# OR_GATE.net
KiCad netlist of a schematic drawn in Altium Designer
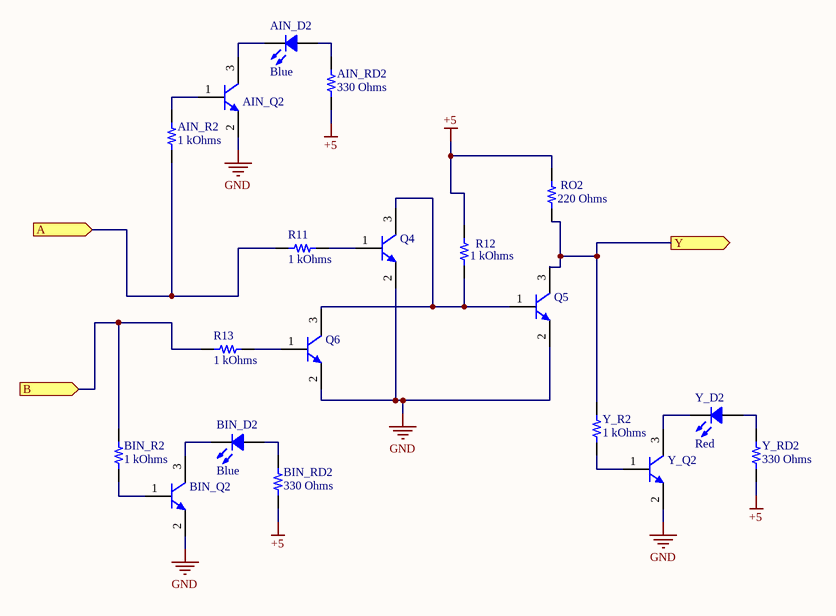
[diagram p0: OR_GATE.SchDoc]

(export (version "E")
  (design (tool "Eeschema 10.0.6"))
  (components
    (comp (ref "AIN_D2")
      (value "Blue")
      (footprint "LED 0603_1608 BLUE")
      (description "LED BLUE CLEAR 0603 SMD")
      (fields (field (name "PART NUMBER") "IN-S63AT5B") (field (name "MANUFACTURER") "Inolux"))
      (libsource (lib "Celestial Altium Library - altium_library") (part "LED"))
    )
    (comp (ref "AIN_Q2")
      (value "MMSS8050-L-TP")
      (footprint "MCCSEMI SOT-23-3")
      (description "TRANS NPN 25V 1.5A SOT23")
      (fields (field (name "MANUFACTURER") "Micro Commercial Co"))
      (libsource (lib "Celestial Altium Library - altium_library") (part "MCCSEMI NPN SOT-23-3"))
    )
    (comp (ref "AIN_R2")
      (value "1 kOhms")
      (footprint "RES 0603_1608")
      (description "RES SMD 1K OHM 0.1% 1/16W 0603")
      (fields
        (field (name "PART NUMBER") "CPF0603B1K0E")
        (field (name "MANUFACTURER") "TE Connectivity Passive Product")
      )
      (libsource (lib "Celestial Altium Library - altium_library") (part "Resistor"))
    )
    (comp (ref "AIN_RD2")
      (value "330 Ohms")
      (footprint "RES 0603_1608")
      (description "RES 330 OHM 5% 1/10W 0603")
      (fields
        (field (name "PART NUMBER") "RMCF0603JT330R")
        (field (name "MANUFACTURER") "Stackpole Electronics Inc")
      )
      (libsource (lib "Celestial Altium Library - altium_library") (part "Resistor"))
    )
    (comp (ref "BIN_D2")
      (value "Blue")
      (footprint "LED 0603_1608 BLUE")
      (description "LED BLUE CLEAR 0603 SMD")
      (fields (field (name "PART NUMBER") "IN-S63AT5B") (field (name "MANUFACTURER") "Inolux"))
      (libsource (lib "Celestial Altium Library - altium_library") (part "LED"))
    )
    (comp (ref "BIN_Q2")
      (value "MMSS8050-L-TP")
      (footprint "MCCSEMI SOT-23-3")
      (description "TRANS NPN 25V 1.5A SOT23")
      (fields (field (name "MANUFACTURER") "Micro Commercial Co"))
      (libsource (lib "Celestial Altium Library - altium_library") (part "MCCSEMI NPN SOT-23-3"))
    )
    (comp (ref "BIN_R2")
      (value "1 kOhms")
      (footprint "RES 0603_1608")
      (description "RES SMD 1K OHM 0.1% 1/16W 0603")
      (fields
        (field (name "PART NUMBER") "CPF0603B1K0E")
        (field (name "MANUFACTURER") "TE Connectivity Passive Product")
      )
      (libsource (lib "Celestial Altium Library - altium_library") (part "Resistor"))
    )
    (comp (ref "BIN_RD2")
      (value "330 Ohms")
      (footprint "RES 0603_1608")
      (description "RES 330 OHM 5% 1/10W 0603")
      (fields
        (field (name "PART NUMBER") "RMCF0603JT330R")
        (field (name "MANUFACTURER") "Stackpole Electronics Inc")
      )
      (libsource (lib "Celestial Altium Library - altium_library") (part "Resistor"))
    )
    (comp (ref "Q4")
      (value "MMSS8050-L-TP")
      (footprint "MCCSEMI SOT-23-3")
      (description "TRANS NPN 25V 1.5A SOT23")
      (fields (field (name "MANUFACTURER") "Micro Commercial Co"))
      (libsource (lib "Celestial Altium Library - altium_library") (part "MCCSEMI NPN SOT-23-3"))
    )
    (comp (ref "Q5")
      (value "MMSS8050-L-TP")
      (footprint "MCCSEMI SOT-23-3")
      (description "TRANS NPN 25V 1.5A SOT23")
      (fields (field (name "MANUFACTURER") "Micro Commercial Co"))
      (libsource (lib "Celestial Altium Library - altium_library") (part "MCCSEMI NPN SOT-23-3"))
    )
    (comp (ref "Q6")
      (value "MMSS8050-L-TP")
      (footprint "MCCSEMI SOT-23-3")
      (description "TRANS NPN 25V 1.5A SOT23")
      (fields (field (name "MANUFACTURER") "Micro Commercial Co"))
      (libsource (lib "Celestial Altium Library - altium_library") (part "MCCSEMI NPN SOT-23-3"))
    )
    (comp (ref "R11")
      (value "1 kOhms")
      (footprint "RES 0603_1608")
      (description "RES SMD 1K OHM 0.1% 1/16W 0603")
      (fields
        (field (name "PART NUMBER") "CPF0603B1K0E")
        (field (name "MANUFACTURER") "TE Connectivity Passive Product")
      )
      (libsource (lib "Celestial Altium Library - altium_library") (part "Resistor"))
    )
    (comp (ref "R12")
      (value "1 kOhms")
      (footprint "RES 0603_1608")
      (description "RES SMD 1K OHM 0.1% 1/16W 0603")
      (fields
        (field (name "PART NUMBER") "CPF0603B1K0E")
        (field (name "MANUFACTURER") "TE Connectivity Passive Product")
      )
      (libsource (lib "Celestial Altium Library - altium_library") (part "Resistor"))
    )
    (comp (ref "R13")
      (value "1 kOhms")
      (footprint "RES 0603_1608")
      (description "RES SMD 1K OHM 0.1% 1/16W 0603")
      (fields
        (field (name "PART NUMBER") "CPF0603B1K0E")
        (field (name "MANUFACTURER") "TE Connectivity Passive Product")
      )
      (libsource (lib "Celestial Altium Library - altium_library") (part "Resistor"))
    )
    (comp (ref "RO2")
      (value "220 Ohms")
      (footprint "RES 0603_1608")
      (description "RES SMD 220 OHM 0.5% 1/10W 0603")
      (fields
        (field (name "PART NUMBER") "ERA-3AED221V")
        (field (name "MANUFACTURER") "Panasonic Electronic Components")
      )
      (libsource (lib "Celestial Altium Library - altium_library") (part "Resistor"))
    )
    (comp (ref "Y_D2")
      (value "Red")
      (footprint "LED 0603_1608 RED")
      (description "LED RED CLEAR CHIP SMD")
      (fields (field (name "PART NUMBER") "XZMDK53W-8") (field (name "MANUFACTURER") "SunLED"))
      (libsource (lib "Celestial Altium Library - altium_library") (part "LED"))
    )
    (comp (ref "Y_Q2")
      (value "MMSS8050-L-TP")
      (footprint "MCCSEMI SOT-23-3")
      (description "TRANS NPN 25V 1.5A SOT23")
      (fields (field (name "MANUFACTURER") "Micro Commercial Co"))
      (libsource (lib "Celestial Altium Library - altium_library") (part "MCCSEMI NPN SOT-23-3"))
    )
    (comp (ref "Y_R2")
      (value "1 kOhms")
      (footprint "RES 0603_1608")
      (description "RES SMD 1K OHM 0.1% 1/16W 0603")
      (fields
        (field (name "PART NUMBER") "CPF0603B1K0E")
        (field (name "MANUFACTURER") "TE Connectivity Passive Product")
      )
      (libsource (lib "Celestial Altium Library - altium_library") (part "Resistor"))
    )
    (comp (ref "Y_RD2")
      (value "330 Ohms")
      (footprint "RES 0603_1608")
      (description "RES 330 OHM 5% 1/10W 0603")
      (fields
        (field (name "PART NUMBER") "RMCF0603JT330R")
        (field (name "MANUFACTURER") "Stackpole Electronics Inc")
      )
      (libsource (lib "Celestial Altium Library - altium_library") (part "Resistor"))
    )
  )
  (nets
    (net (code "1") (name "+5") (class "Default")
      (node (ref "AIN_RD2") (pin "1") (pinfunction "1_1") (pintype "passive"))
      (node (ref "BIN_RD2") (pin "1") (pinfunction "1_1") (pintype "passive"))
      (node (ref "R12") (pin "2") (pinfunction "2_2") (pintype "passive"))
      (node (ref "RO2") (pin "2") (pinfunction "2_2") (pintype "passive"))
      (node (ref "Y_RD2") (pin "1") (pinfunction "1_1") (pintype "passive"))
    )
    (net (code "2") (name "/A") (class "Default")
      (node (ref "AIN_R2") (pin "2") (pinfunction "2_2") (pintype "passive"))
      (node (ref "R11") (pin "1") (pinfunction "1_1") (pintype "passive"))
    )
    (net (code "3") (name "/B") (class "Default")
      (node (ref "BIN_R2") (pin "2") (pinfunction "2_2") (pintype "passive"))
      (node (ref "R13") (pin "1") (pinfunction "1_1") (pintype "passive"))
    )
    (net (code "4") (name "/Y") (class "Default")
      (node (ref "Q5") (pin "3") (pinfunction "C_3") (pintype "passive"))
      (node (ref "RO2") (pin "1") (pinfunction "1_1") (pintype "passive"))
      (node (ref "Y_R2") (pin "2") (pinfunction "2_2") (pintype "passive"))
    )
    (net (code "5") (name "GND") (class "Default")
      (node (ref "AIN_Q2") (pin "2") (pinfunction "E_2") (pintype "passive"))
      (node (ref "BIN_Q2") (pin "2") (pinfunction "E_2") (pintype "passive"))
      (node (ref "Q4") (pin "2") (pinfunction "E_2") (pintype "passive"))
      (node (ref "Q5") (pin "2") (pinfunction "E_2") (pintype "passive"))
      (node (ref "Q6") (pin "2") (pinfunction "E_2") (pintype "passive"))
      (node (ref "Y_Q2") (pin "2") (pinfunction "E_2") (pintype "passive"))
    )
    (net (code "6") (name "Net-(AIN_D2-Pad1)") (class "Default")
      (node (ref "AIN_D2") (pin "1") (pinfunction "1_1") (pintype "passive"))
      (node (ref "AIN_RD2") (pin "2") (pinfunction "2_2") (pintype "passive"))
    )
    (net (code "7") (name "Net-(AIN_Q2-B)") (class "Default")
      (node (ref "AIN_Q2") (pin "1") (pinfunction "B_1") (pintype "passive"))
      (node (ref "AIN_R2") (pin "1") (pinfunction "1_1") (pintype "passive"))
    )
    (net (code "8") (name "Net-(AIN_Q2-C)") (class "Default")
      (node (ref "AIN_D2") (pin "2") (pinfunction "2_2") (pintype "passive"))
      (node (ref "AIN_Q2") (pin "3") (pinfunction "C_3") (pintype "passive"))
    )
    (net (code "9") (name "Net-(BIN_D2-Pad1)") (class "Default")
      (node (ref "BIN_D2") (pin "1") (pinfunction "1_1") (pintype "passive"))
      (node (ref "BIN_RD2") (pin "2") (pinfunction "2_2") (pintype "passive"))
    )
    (net (code "10") (name "Net-(BIN_Q2-B)") (class "Default")
      (node (ref "BIN_Q2") (pin "1") (pinfunction "B_1") (pintype "passive"))
      (node (ref "BIN_R2") (pin "1") (pinfunction "1_1") (pintype "passive"))
    )
    (net (code "11") (name "Net-(BIN_Q2-C)") (class "Default")
      (node (ref "BIN_D2") (pin "2") (pinfunction "2_2") (pintype "passive"))
      (node (ref "BIN_Q2") (pin "3") (pinfunction "C_3") (pintype "passive"))
    )
    (net (code "12") (name "Net-(Q4-B)") (class "Default")
      (node (ref "Q4") (pin "1") (pinfunction "B_1") (pintype "passive"))
      (node (ref "R11") (pin "2") (pinfunction "2_2") (pintype "passive"))
    )
    (net (code "13") (name "Net-(Q4-C)") (class "Default")
      (node (ref "Q4") (pin "3") (pinfunction "C_3") (pintype "passive"))
      (node (ref "Q5") (pin "1") (pinfunction "B_1") (pintype "passive"))
      (node (ref "Q6") (pin "3") (pinfunction "C_3") (pintype "passive"))
      (node (ref "R12") (pin "1") (pinfunction "1_1") (pintype "passive"))
    )
    (net (code "14") (name "Net-(Q6-B)") (class "Default")
      (node (ref "Q6") (pin "1") (pinfunction "B_1") (pintype "passive"))
      (node (ref "R13") (pin "2") (pinfunction "2_2") (pintype "passive"))
    )
    (net (code "15") (name "Net-(Y_D2-Pad1)") (class "Default")
      (node (ref "Y_D2") (pin "1") (pinfunction "1_1") (pintype "passive"))
      (node (ref "Y_RD2") (pin "2") (pinfunction "2_2") (pintype "passive"))
    )
    (net (code "16") (name "Net-(Y_Q2-B)") (class "Default")
      (node (ref "Y_Q2") (pin "1") (pinfunction "B_1") (pintype "passive"))
      (node (ref "Y_R2") (pin "1") (pinfunction "1_1") (pintype "passive"))
    )
    (net (code "17") (name "Net-(Y_Q2-C)") (class "Default")
      (node (ref "Y_D2") (pin "2") (pinfunction "2_2") (pintype "passive"))
      (node (ref "Y_Q2") (pin "3") (pinfunction "C_3") (pintype "passive"))
    )
  )
)
